# design.net
KiCad netlist of a schematic drawn in Altium Designer
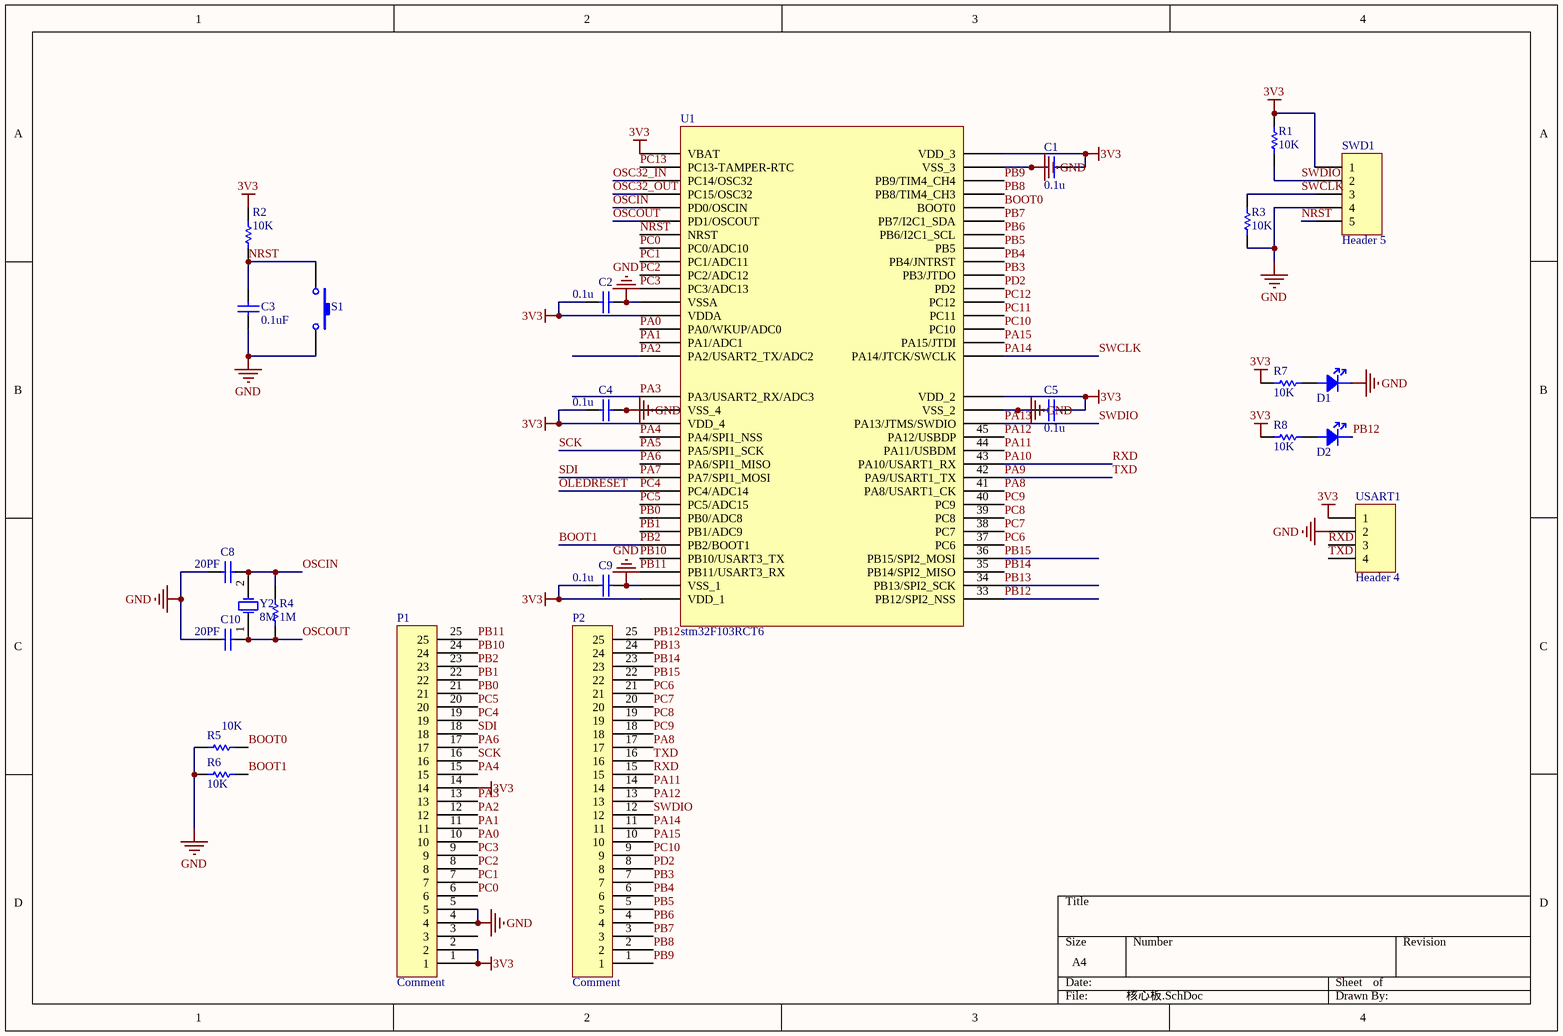
[diagram p0: 核心板.SchDoc]

(export (version "E")
  (design (tool "Eeschema 10.0.6"))
  (components
    (comp (ref "C1")
      (value "0.1u")
      (footprint "CAP-MLCC-0603")
      (description "Capacitor")
      (fields (field (name "Comment") "Cap") (field (name "PUBLISHER") "Altium Limited"))
      (libsource (lib "K60-mainboard-v3.1") (part "Cap_1"))
    )
    (comp (ref "C2")
      (value "0.1u")
      (footprint "CAP-MLCC-0603")
      (description "Capacitor")
      (fields (field (name "Comment") "Cap") (field (name "PUBLISHER") "Altium Limited"))
      (libsource (lib "K60-mainboard-v3.1") (part "Cap_1"))
    )
    (comp (ref "C3")
      (value "0.1uF")
      (footprint "CAP-MLCC-0603")
      (description "Capacitor")
      (fields (field (name "Comment") "Cap") (field (name "PUBLISHER") "Altium Limited"))
      (libsource (lib "K60-mainboard-v3.1") (part "Cap"))
    )
    (comp (ref "C4")
      (value "0.1u")
      (footprint "CAP-MLCC-0603")
      (description "Capacitor")
      (fields (field (name "Comment") "Cap") (field (name "PUBLISHER") "Altium Limited"))
      (libsource (lib "K60-mainboard-v3.1") (part "Cap_1"))
    )
    (comp (ref "C5")
      (value "0.1u")
      (footprint "CAP-MLCC-0603")
      (description "Capacitor")
      (fields (field (name "Comment") "Cap") (field (name "PUBLISHER") "Altium Limited"))
      (libsource (lib "K60-mainboard-v3.1") (part "Cap_1"))
    )
    (comp (ref "C8")
      (value "20PF")
      (footprint "CAP-MLCC-0603")
      (description "Capacitor")
      (fields (field (name "Comment") "Cap") (field (name "PUBLISHER") "Altium Limited"))
      (libsource (lib "K60-mainboard-v3.1") (part "Cap_1"))
    )
    (comp (ref "C9")
      (value "0.1u")
      (footprint "CAP-MLCC-0603")
      (description "Capacitor")
      (fields (field (name "Comment") "Cap") (field (name "PUBLISHER") "Altium Limited"))
      (libsource (lib "K60-mainboard-v3.1") (part "Cap_1"))
    )
    (comp (ref "C10")
      (value "20PF")
      (footprint "CAP-MLCC-0603")
      (description "Capacitor")
      (fields (field (name "Comment") "Cap") (field (name "PUBLISHER") "Altium Limited"))
      (libsource (lib "K60-mainboard-v3.1") (part "Cap_1"))
    )
    (comp (ref "D1")
      (value "lED")
      (footprint "0805D")
      (description "LED")
      (libsource (lib "K60-mainboard-v3.1") (part "00-D-LED"))
    )
    (comp (ref "D2")
      (value "lED")
      (footprint "0805D")
      (description "LED")
      (libsource (lib "K60-mainboard-v3.1") (part "00-D-LED"))
    )
    (comp (ref "P1")
      (value "Comment")
      (footprint "HDR1X25_1.27")
      (description "Header, 25-Pin")
      (fields (field (name "PUBLISHER") "Altium Limited"))
      (libsource (lib "K60-mainboard-v3.1") (part "Header 25"))
    )
    (comp (ref "P2")
      (value "Comment")
      (footprint "HDR1X25_1.27")
      (description "Header, 25-Pin")
      (fields (field (name "PUBLISHER") "Altium Limited"))
      (libsource (lib "K60-mainboard-v3.1") (part "Header 25"))
    )
    (comp (ref "R1")
      (value "10K")
      (footprint "RES-0603")
      (description "Resistor")
      (fields (field (name "Comment") "Res1") (field (name "PUBLISHER") "Altium Limited"))
      (libsource (lib "K60-mainboard-v3.1") (part "Res1_1"))
    )
    (comp (ref "R2")
      (value "10K")
      (footprint "RES-0603")
      (description "Resistor")
      (fields (field (name "Comment") "Res1") (field (name "PUBLISHER") "Altium Limited"))
      (libsource (lib "K60-mainboard-v3.1") (part "Res1_1"))
    )
    (comp (ref "R3")
      (value "10K")
      (footprint "RES-0603")
      (description "Resistor")
      (fields (field (name "Comment") "Res1") (field (name "PUBLISHER") "Altium Limited"))
      (libsource (lib "K60-mainboard-v3.1") (part "Res1_1"))
    )
    (comp (ref "R4")
      (value "1M")
      (footprint "RES-0603")
      (description "Resistor")
      (fields (field (name "Comment") "Res1") (field (name "PUBLISHER") "Altium Limited"))
      (libsource (lib "K60-mainboard-v3.1") (part "Res1_1"))
    )
    (comp (ref "R5")
      (value "10K")
      (footprint "RES-0603")
      (description "Resistor")
      (fields (field (name "Comment") "Res1") (field (name "PUBLISHER") "Altium Limited"))
      (libsource (lib "K60-mainboard-v3.1") (part "Res1_1"))
    )
    (comp (ref "R6")
      (value "10K")
      (footprint "RES-0603")
      (description "Resistor")
      (fields (field (name "Comment") "Res1") (field (name "PUBLISHER") "Altium Limited"))
      (libsource (lib "K60-mainboard-v3.1") (part "Res1_1"))
    )
    (comp (ref "R7")
      (value "10K")
      (footprint "RES-0603")
      (description "Resistor")
      (fields (field (name "Comment") "Res1") (field (name "PUBLISHER") "Altium Limited"))
      (libsource (lib "K60-mainboard-v3.1") (part "Res1_1"))
    )
    (comp (ref "R8")
      (value "10K")
      (footprint "RES-0603")
      (description "Resistor")
      (fields (field (name "Comment") "Res1") (field (name "PUBLISHER") "Altium Limited"))
      (libsource (lib "K60-mainboard-v3.1") (part "Res1_1"))
    )
    (comp (ref "S1")
      (value "SW-PB")
      (footprint "key - duplicate")
      (description "Switch")
      (fields (field (name "PUBLISHER") "Altium Limited"))
      (libsource (lib "附加元件") (part "SW-PB"))
    )
    (comp (ref "SWD1")
      (value "Header 5")
      (footprint "HDR1X5")
      (description "Header, 5-Pin")
      (fields (field (name "PUBLISHER") "Altium Limited"))
      (libsource (lib "K60-mainboard-v3.1") (part "Header 5"))
    )
    (comp (ref "U1")
      (value "stm32F103RCT6")
      (footprint "STM32F103RCT6")
      (libsource (lib "K60-mainboard-v3.1") (part "stm32F103RCT6"))
    )
    (comp (ref "USART1")
      (value "Header 4")
      (footprint "HDR1X4")
      (description "Header, 4-Pin")
      (fields (field (name "PUBLISHER") "Altium Limited"))
      (libsource (lib "K60-mainboard-v3.1") (part "Header 4"))
    )
    (comp (ref "Y2")
      (value "8M")
      (footprint "Libraries_2014_0618:Osc-6032")
      (description "Crystal Oscillator")
      (fields (field (name "PUBLISHER") "Altium Limited"))
      (libsource (lib "Libraries_2014_0618") (part "C-Osc"))
    )
  )
  (nets
    (net (code "1") (name "/BOOT0") (class "Default")
      (node (ref "R5") (pin "1") (pinfunction "1_1") (pintype "passive"))
      (node (ref "U1") (pin "60") (pinfunction "BOOT0_60") (pintype "passive"))
    )
    (net (code "2") (name "/BOOT1") (class "Default")
      (node (ref "P1") (pin "23") (pinfunction "23_23") (pintype "passive"))
      (node (ref "R6") (pin "1") (pinfunction "1_1") (pintype "passive"))
      (node (ref "U1") (pin "28") (pinfunction "PB2/BOOT1_28") (pintype "passive"))
    )
    (net (code "3") (name "/NRST") (class "Default")
      (node (ref "C3") (pin "1") (pinfunction "1_1") (pintype "passive"))
      (node (ref "R2") (pin "1") (pinfunction "1_1") (pintype "passive"))
      (node (ref "S1") (pin "1") (pinfunction "1_1") (pintype "passive"))
      (node (ref "SWD1") (pin "5") (pinfunction "5_5") (pintype "passive"))
      (node (ref "U1") (pin "7") (pinfunction "NRST_7") (pintype "passive"))
    )
    (net (code "4") (name "/OLEDRESET") (class "Default")
      (node (ref "P1") (pin "19") (pinfunction "19_19") (pintype "passive"))
      (node (ref "U1") (pin "24") (pinfunction "PC4/ADC14_24") (pintype "passive"))
    )
    (net (code "5") (name "/OSC32_IN") (class "Default")
      (node (ref "U1") (pin "3") (pinfunction "PC14/OSC32_3") (pintype "passive"))
    )
    (net (code "6") (name "/OSC32_OUT") (class "Default")
      (node (ref "U1") (pin "4") (pinfunction "PC15/OSC32_4") (pintype "passive"))
    )
    (net (code "7") (name "/OSCIN") (class "Default")
      (node (ref "C8") (pin "2") (pinfunction "2_2") (pintype "passive"))
      (node (ref "R4") (pin "2") (pinfunction "2_2") (pintype "passive"))
      (node (ref "U1") (pin "5") (pinfunction "PD0/OSCIN_5") (pintype "passive"))
      (node (ref "Y2") (pin "2") (pinfunction "OSC2_2") (pintype "passive"))
    )
    (net (code "8") (name "/OSCOUT") (class "Default")
      (node (ref "C10") (pin "2") (pinfunction "2_2") (pintype "passive"))
      (node (ref "R4") (pin "1") (pinfunction "1_1") (pintype "passive"))
      (node (ref "U1") (pin "6") (pinfunction "PD1/OSCOUT_6") (pintype "passive"))
      (node (ref "Y2") (pin "1") (pinfunction "OSC1_1") (pintype "passive"))
    )
    (net (code "9") (name "/PA0") (class "Default")
      (node (ref "P1") (pin "10") (pinfunction "10_10") (pintype "passive"))
      (node (ref "U1") (pin "14") (pinfunction "PA0/WKUP/ADC0_14") (pintype "passive"))
    )
    (net (code "10") (name "/PA1") (class "Default")
      (node (ref "P1") (pin "11") (pinfunction "11_11") (pintype "passive"))
      (node (ref "U1") (pin "15") (pinfunction "PA1/ADC1_15") (pintype "passive"))
    )
    (net (code "11") (name "/PA2") (class "Default")
      (node (ref "P1") (pin "12") (pinfunction "12_12") (pintype "passive"))
      (node (ref "U1") (pin "16") (pinfunction "PA2/USART2_TX/ADC2_16") (pintype "passive"))
    )
    (net (code "12") (name "/PA3") (class "Default")
      (node (ref "P1") (pin "13") (pinfunction "13_13") (pintype "passive"))
      (node (ref "U1") (pin "17") (pinfunction "PA3/USART2_RX/ADC3_17") (pintype "passive"))
    )
    (net (code "13") (name "/PA4") (class "Default")
      (node (ref "P1") (pin "15") (pinfunction "15_15") (pintype "passive"))
      (node (ref "U1") (pin "20") (pinfunction "PA4/SPI1_NSS_20") (pintype "passive"))
    )
    (net (code "14") (name "/PA5") (class "Default")
      (node (ref "P1") (pin "16") (pinfunction "16_16") (pintype "passive"))
      (node (ref "U1") (pin "21") (pinfunction "PA5/SPI1_SCK_21") (pintype "passive"))
    )
    (net (code "15") (name "/PA6") (class "Default")
      (node (ref "P1") (pin "17") (pinfunction "17_17") (pintype "passive"))
      (node (ref "U1") (pin "22") (pinfunction "PA6/SPI1_MISO_22") (pintype "passive"))
    )
    (net (code "16") (name "/PA7") (class "Default")
      (node (ref "P1") (pin "18") (pinfunction "18_18") (pintype "passive"))
      (node (ref "U1") (pin "23") (pinfunction "PA7/SPI1_MOSI_23") (pintype "passive"))
    )
    (net (code "17") (name "/PA8") (class "Default")
      (node (ref "P2") (pin "17") (pinfunction "17_17") (pintype "passive"))
      (node (ref "U1") (pin "41") (pinfunction "PA8/USART1_CK_41") (pintype "passive"))
    )
    (net (code "18") (name "/PA9") (class "Default")
      (node (ref "P2") (pin "16") (pinfunction "16_16") (pintype "passive"))
      (node (ref "U1") (pin "42") (pinfunction "PA9/USART1_TX_42") (pintype "passive"))
      (node (ref "USART1") (pin "4") (pinfunction "4_4") (pintype "passive"))
    )
    (net (code "19") (name "/PA10") (class "Default")
      (node (ref "P2") (pin "15") (pinfunction "15_15") (pintype "passive"))
      (node (ref "U1") (pin "43") (pinfunction "PA10/USART1_RX_43") (pintype "passive"))
      (node (ref "USART1") (pin "3") (pinfunction "3_3") (pintype "passive"))
    )
    (net (code "20") (name "/PA11") (class "Default")
      (node (ref "P2") (pin "14") (pinfunction "14_14") (pintype "passive"))
      (node (ref "U1") (pin "44") (pinfunction "PA11/USBDM_44") (pintype "passive"))
    )
    (net (code "21") (name "/PA12") (class "Default")
      (node (ref "P2") (pin "13") (pinfunction "13_13") (pintype "passive"))
      (node (ref "U1") (pin "45") (pinfunction "PA12/USBDP_45") (pintype "passive"))
    )
    (net (code "22") (name "/PA13") (class "Default")
      (node (ref "P2") (pin "12") (pinfunction "12_12") (pintype "passive"))
      (node (ref "R1") (pin "1") (pinfunction "1_1") (pintype "passive"))
      (node (ref "SWD1") (pin "2") (pinfunction "2_2") (pintype "passive"))
      (node (ref "U1") (pin "46") (pinfunction "PA13/JTMS/SWDIO_46") (pintype "passive"))
    )
    (net (code "23") (name "/PA14") (class "Default")
      (node (ref "P2") (pin "11") (pinfunction "11_11") (pintype "passive"))
      (node (ref "R3") (pin "1") (pinfunction "1_1") (pintype "passive"))
      (node (ref "SWD1") (pin "3") (pinfunction "3_3") (pintype "passive"))
      (node (ref "U1") (pin "49") (pinfunction "PA14/JTCK/SWCLK_49") (pintype "passive"))
    )
    (net (code "24") (name "/PA15") (class "Default")
      (node (ref "P2") (pin "10") (pinfunction "10_10") (pintype "passive"))
      (node (ref "U1") (pin "50") (pinfunction "PA15/JTDI_50") (pintype "passive"))
    )
    (net (code "25") (name "/PB0") (class "Default")
      (node (ref "P1") (pin "21") (pinfunction "21_21") (pintype "passive"))
      (node (ref "U1") (pin "26") (pinfunction "PB0/ADC8_26") (pintype "passive"))
    )
    (net (code "26") (name "/PB1") (class "Default")
      (node (ref "P1") (pin "22") (pinfunction "22_22") (pintype "passive"))
      (node (ref "U1") (pin "27") (pinfunction "PB1/ADC9_27") (pintype "passive"))
    )
    (net (code "27") (name "/PB3") (class "Default")
      (node (ref "P2") (pin "7") (pinfunction "7_7") (pintype "passive"))
      (node (ref "U1") (pin "55") (pinfunction "PB3/JTDO_55") (pintype "passive"))
    )
    (net (code "28") (name "/PB4") (class "Default")
      (node (ref "P2") (pin "6") (pinfunction "6_6") (pintype "passive"))
      (node (ref "U1") (pin "56") (pinfunction "PB4/JNTRST_56") (pintype "passive"))
    )
    (net (code "29") (name "/PB5") (class "Default")
      (node (ref "P2") (pin "5") (pinfunction "5_5") (pintype "passive"))
      (node (ref "U1") (pin "57") (pinfunction "PB5_57") (pintype "passive"))
    )
    (net (code "30") (name "/PB6") (class "Default")
      (node (ref "P2") (pin "4") (pinfunction "4_4") (pintype "passive"))
      (node (ref "U1") (pin "58") (pinfunction "PB6/I2C1_SCL_58") (pintype "passive"))
    )
    (net (code "31") (name "/PB7") (class "Default")
      (node (ref "P2") (pin "3") (pinfunction "3_3") (pintype "passive"))
      (node (ref "U1") (pin "59") (pinfunction "PB7/I2C1_SDA_59") (pintype "passive"))
    )
    (net (code "32") (name "/PB8") (class "Default")
      (node (ref "P2") (pin "2") (pinfunction "2_2") (pintype "passive"))
      (node (ref "U1") (pin "61") (pinfunction "PB8/TIM4_CH3_61") (pintype "passive"))
    )
    (net (code "33") (name "/PB9") (class "Default")
      (node (ref "P2") (pin "1") (pinfunction "1_1") (pintype "passive"))
      (node (ref "U1") (pin "62") (pinfunction "PB9/TIM4_CH4_62") (pintype "passive"))
    )
    (net (code "34") (name "/PB10") (class "Default")
      (node (ref "P1") (pin "24") (pinfunction "24_24") (pintype "passive"))
      (node (ref "U1") (pin "29") (pinfunction "PB10/USART3_TX_29") (pintype "passive"))
    )
    (net (code "35") (name "/PB11") (class "Default")
      (node (ref "P1") (pin "25") (pinfunction "25_25") (pintype "passive"))
      (node (ref "U1") (pin "30") (pinfunction "PB11/USART3_RX_30") (pintype "passive"))
    )
    (net (code "36") (name "/PB12") (class "Default")
      (node (ref "D2") (pin "K") (pinfunction "2_K") (pintype "passive"))
      (node (ref "P2") (pin "25") (pinfunction "25_25") (pintype "passive"))
      (node (ref "U1") (pin "33") (pinfunction "PB12/SPI2_NSS_33") (pintype "passive"))
    )
    (net (code "37") (name "/PB13") (class "Default")
      (node (ref "P2") (pin "24") (pinfunction "24_24") (pintype "passive"))
      (node (ref "U1") (pin "34") (pinfunction "PB13/SPI2_SCK_34") (pintype "passive"))
    )
    (net (code "38") (name "/PB14") (class "Default")
      (node (ref "P2") (pin "23") (pinfunction "23_23") (pintype "passive"))
      (node (ref "U1") (pin "35") (pinfunction "PB14/SPI2_MISO_35") (pintype "passive"))
    )
    (net (code "39") (name "/PB15") (class "Default")
      (node (ref "P2") (pin "22") (pinfunction "22_22") (pintype "passive"))
      (node (ref "U1") (pin "36") (pinfunction "PB15/SPI2_MOSI_36") (pintype "passive"))
    )
    (net (code "40") (name "/PC0") (class "Default")
      (node (ref "P1") (pin "6") (pinfunction "6_6") (pintype "passive"))
      (node (ref "U1") (pin "8") (pinfunction "PC0/ADC10_8") (pintype "passive"))
    )
    (net (code "41") (name "/PC1") (class "Default")
      (node (ref "P1") (pin "7") (pinfunction "7_7") (pintype "passive"))
      (node (ref "U1") (pin "9") (pinfunction "PC1/ADC11_9") (pintype "passive"))
    )
    (net (code "42") (name "/PC2") (class "Default")
      (node (ref "P1") (pin "8") (pinfunction "8_8") (pintype "passive"))
      (node (ref "U1") (pin "10") (pinfunction "PC2/ADC12_10") (pintype "passive"))
    )
    (net (code "43") (name "/PC3") (class "Default")
      (node (ref "P1") (pin "9") (pinfunction "9_9") (pintype "passive"))
      (node (ref "U1") (pin "11") (pinfunction "PC3/ADC13_11") (pintype "passive"))
    )
    (net (code "44") (name "/PC5") (class "Default")
      (node (ref "P1") (pin "20") (pinfunction "20_20") (pintype "passive"))
      (node (ref "U1") (pin "25") (pinfunction "PC5/ADC15_25") (pintype "passive"))
    )
    (net (code "45") (name "/PC6") (class "Default")
      (node (ref "P2") (pin "21") (pinfunction "21_21") (pintype "passive"))
      (node (ref "U1") (pin "37") (pinfunction "PC6_37") (pintype "passive"))
    )
    (net (code "46") (name "/PC7") (class "Default")
      (node (ref "P2") (pin "20") (pinfunction "20_20") (pintype "passive"))
      (node (ref "U1") (pin "38") (pinfunction "PC7_38") (pintype "passive"))
    )
    (net (code "47") (name "/PC8") (class "Default")
      (node (ref "P2") (pin "19") (pinfunction "19_19") (pintype "passive"))
      (node (ref "U1") (pin "39") (pinfunction "PC8_39") (pintype "passive"))
    )
    (net (code "48") (name "/PC9") (class "Default")
      (node (ref "P2") (pin "18") (pinfunction "18_18") (pintype "passive"))
      (node (ref "U1") (pin "40") (pinfunction "PC9_40") (pintype "passive"))
    )
    (net (code "49") (name "/PC10") (class "Default")
      (node (ref "P2") (pin "9") (pinfunction "9_9") (pintype "passive"))
      (node (ref "U1") (pin "51") (pinfunction "PC10_51") (pintype "passive"))
    )
    (net (code "50") (name "/PC11") (class "Default")
      (node (ref "U1") (pin "52") (pinfunction "PC11_52") (pintype "passive"))
    )
    (net (code "51") (name "/PC12") (class "Default")
      (node (ref "U1") (pin "53") (pinfunction "PC12_53") (pintype "passive"))
    )
    (net (code "52") (name "/PC13") (class "Default")
      (node (ref "U1") (pin "2") (pinfunction "PC13-TAMPER-RTC_2") (pintype "passive"))
    )
    (net (code "53") (name "/PD2") (class "Default")
      (node (ref "P2") (pin "8") (pinfunction "8_8") (pintype "passive"))
      (node (ref "U1") (pin "54") (pinfunction "PD2_54") (pintype "passive"))
    )
    (net (code "54") (name "3V3") (class "Default")
      (node (ref "C1") (pin "1") (pinfunction "1_1") (pintype "passive"))
      (node (ref "C2") (pin "1") (pinfunction "1_1") (pintype "passive"))
      (node (ref "C4") (pin "1") (pinfunction "1_1") (pintype "passive"))
      (node (ref "C5") (pin "1") (pinfunction "1_1") (pintype "passive"))
      (node (ref "C9") (pin "1") (pinfunction "1_1") (pintype "passive"))
      (node (ref "P1") (pin "1") (pinfunction "1_1") (pintype "passive"))
      (node (ref "P1") (pin "14") (pinfunction "14_14") (pintype "passive"))
      (node (ref "P1") (pin "2") (pinfunction "2_2") (pintype "passive"))
      (node (ref "R1") (pin "2") (pinfunction "2_2") (pintype "passive"))
      (node (ref "R2") (pin "2") (pinfunction "2_2") (pintype "passive"))
      (node (ref "R7") (pin "2") (pinfunction "2_2") (pintype "passive"))
      (node (ref "R8") (pin "2") (pinfunction "2_2") (pintype "passive"))
      (node (ref "SWD1") (pin "1") (pinfunction "1_1") (pintype "passive"))
      (node (ref "U1") (pin "1") (pinfunction "VBAT_1") (pintype "passive"))
      (node (ref "U1") (pin "13") (pinfunction "VDDA_13") (pintype "passive"))
      (node (ref "U1") (pin "19") (pinfunction "VDD_4_19") (pintype "passive"))
      (node (ref "U1") (pin "32") (pinfunction "VDD_1_32") (pintype "passive"))
      (node (ref "U1") (pin "48") (pinfunction "VDD_2_48") (pintype "passive"))
      (node (ref "U1") (pin "64") (pinfunction "VDD_3_64") (pintype "passive"))
      (node (ref "USART1") (pin "1") (pinfunction "1_1") (pintype "passive"))
    )
    (net (code "55") (name "GND") (class "Default")
      (node (ref "C1") (pin "2") (pinfunction "2_2") (pintype "passive"))
      (node (ref "C10") (pin "1") (pinfunction "1_1") (pintype "passive"))
      (node (ref "C2") (pin "2") (pinfunction "2_2") (pintype "passive"))
      (node (ref "C3") (pin "2") (pinfunction "2_2") (pintype "passive"))
      (node (ref "C4") (pin "2") (pinfunction "2_2") (pintype "passive"))
      (node (ref "C5") (pin "2") (pinfunction "2_2") (pintype "passive"))
      (node (ref "C8") (pin "1") (pinfunction "1_1") (pintype "passive"))
      (node (ref "C9") (pin "2") (pinfunction "2_2") (pintype "passive"))
      (node (ref "D1") (pin "K") (pinfunction "2_K") (pintype "passive"))
      (node (ref "P1") (pin "4") (pinfunction "4_4") (pintype "passive"))
      (node (ref "P1") (pin "5") (pinfunction "5_5") (pintype "passive"))
      (node (ref "R3") (pin "2") (pinfunction "2_2") (pintype "passive"))
      (node (ref "R5") (pin "2") (pinfunction "2_2") (pintype "passive"))
      (node (ref "R6") (pin "2") (pinfunction "2_2") (pintype "passive"))
      (node (ref "S1") (pin "2") (pinfunction "2_2") (pintype "passive"))
      (node (ref "SWD1") (pin "4") (pinfunction "4_4") (pintype "passive"))
      (node (ref "U1") (pin "12") (pinfunction "VSSA_12") (pintype "passive"))
      (node (ref "U1") (pin "18") (pinfunction "VSS_4_18") (pintype "passive"))
      (node (ref "U1") (pin "31") (pinfunction "VSS_1_31") (pintype "passive"))
      (node (ref "U1") (pin "47") (pinfunction "VSS_2_47") (pintype "passive"))
      (node (ref "U1") (pin "63") (pinfunction "VSS_3_63") (pintype "passive"))
      (node (ref "USART1") (pin "2") (pinfunction "2_2") (pintype "passive"))
    )
    (net (code "56") (name "Net-(D1-1)") (class "Default")
      (node (ref "D1") (pin "A") (pinfunction "1_A") (pintype "passive"))
      (node (ref "R7") (pin "1") (pinfunction "1_1") (pintype "passive"))
    )
    (net (code "57") (name "Net-(D2-1)") (class "Default")
      (node (ref "D2") (pin "A") (pinfunction "1_A") (pintype "passive"))
      (node (ref "R8") (pin "1") (pinfunction "1_1") (pintype "passive"))
    )
    (net (code "58") (name "unconnected-(P1-Pad3)") (class "Default")
      (node (ref "P1") (pin "3") (pinfunction "3_3") (pintype "passive"))
    )
  )
)
